# sample_and_hold.net
KiCad netlist of a schematic drawn in EAGLE
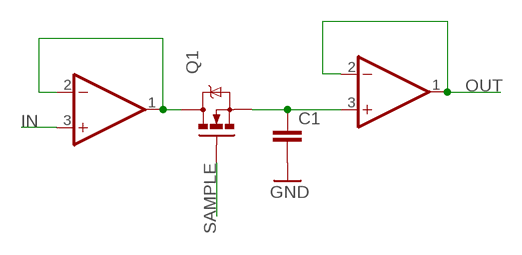
[diagram p0: schematic, sheet 1]

(export (version "E")
  (design (tool "Eeschema 10.0.6"))
  (components
    (comp (ref "C1")
      (value "CAP0402-CAP")
      (footprint "eagle-import:0402-CAP")
      (libsource (lib "eagle-import") (part "CAP0402-CAP"))
    )
    (comp (ref "IC1")
      (value "MCP6022")
      (footprint "eagle-import:SOIC8_150MIL")
      (libsource (lib "eagle-import") (part "MCP6022"))
    )
    (comp (ref "IC2")
      (value "MCP6022")
      (footprint "eagle-import:SOIC8_150MIL")
      (libsource (lib "eagle-import") (part "MCP6022"))
    )
    (comp (ref "Q1")
      (value "MOSFET-NCHANNEL2N7000")
      (footprint "eagle-import:TO-92")
      (libsource (lib "eagle-import") (part "MOSFET-NCHANNEL2N7000"))
    )
  )
  (nets
    (net (code "1") (name "/IN") (class "Default")
      (node (ref "IC1") (pin "3") (pinfunction "+IN_3") (pintype "input"))
    )
    (net (code "2") (name "/OUT") (class "Default")
      (node (ref "IC2") (pin "1") (pinfunction "OUT_1") (pintype "output"))
      (node (ref "IC2") (pin "2") (pinfunction "-IN_2") (pintype "input"))
    )
    (net (code "3") (name "/SAMPLE") (class "Default")
      (node (ref "Q1") (pin "2") (pinfunction "G_2") (pintype "passive"))
    )
    (net (code "4") (name "GND") (class "Default")
      (node (ref "C1") (pin "2") (pinfunction "2_2") (pintype "passive"))
    )
    (net (code "5") (name "Net-(IC1A--IN)") (class "Default")
      (node (ref "IC1") (pin "1") (pinfunction "OUT_1") (pintype "output"))
      (node (ref "IC1") (pin "2") (pinfunction "-IN_2") (pintype "input"))
      (node (ref "Q1") (pin "3") (pinfunction "D_3") (pintype "passive"))
    )
    (net (code "6") (name "Net-(IC2A-+IN)") (class "Default")
      (node (ref "C1") (pin "1") (pinfunction "1_1") (pintype "passive"))
      (node (ref "IC2") (pin "3") (pinfunction "+IN_3") (pintype "input"))
      (node (ref "Q1") (pin "1") (pinfunction "S_1") (pintype "passive"))
    )
  )
)
